# design.net
KiCad netlist of a schematic drawn in Altium Designer
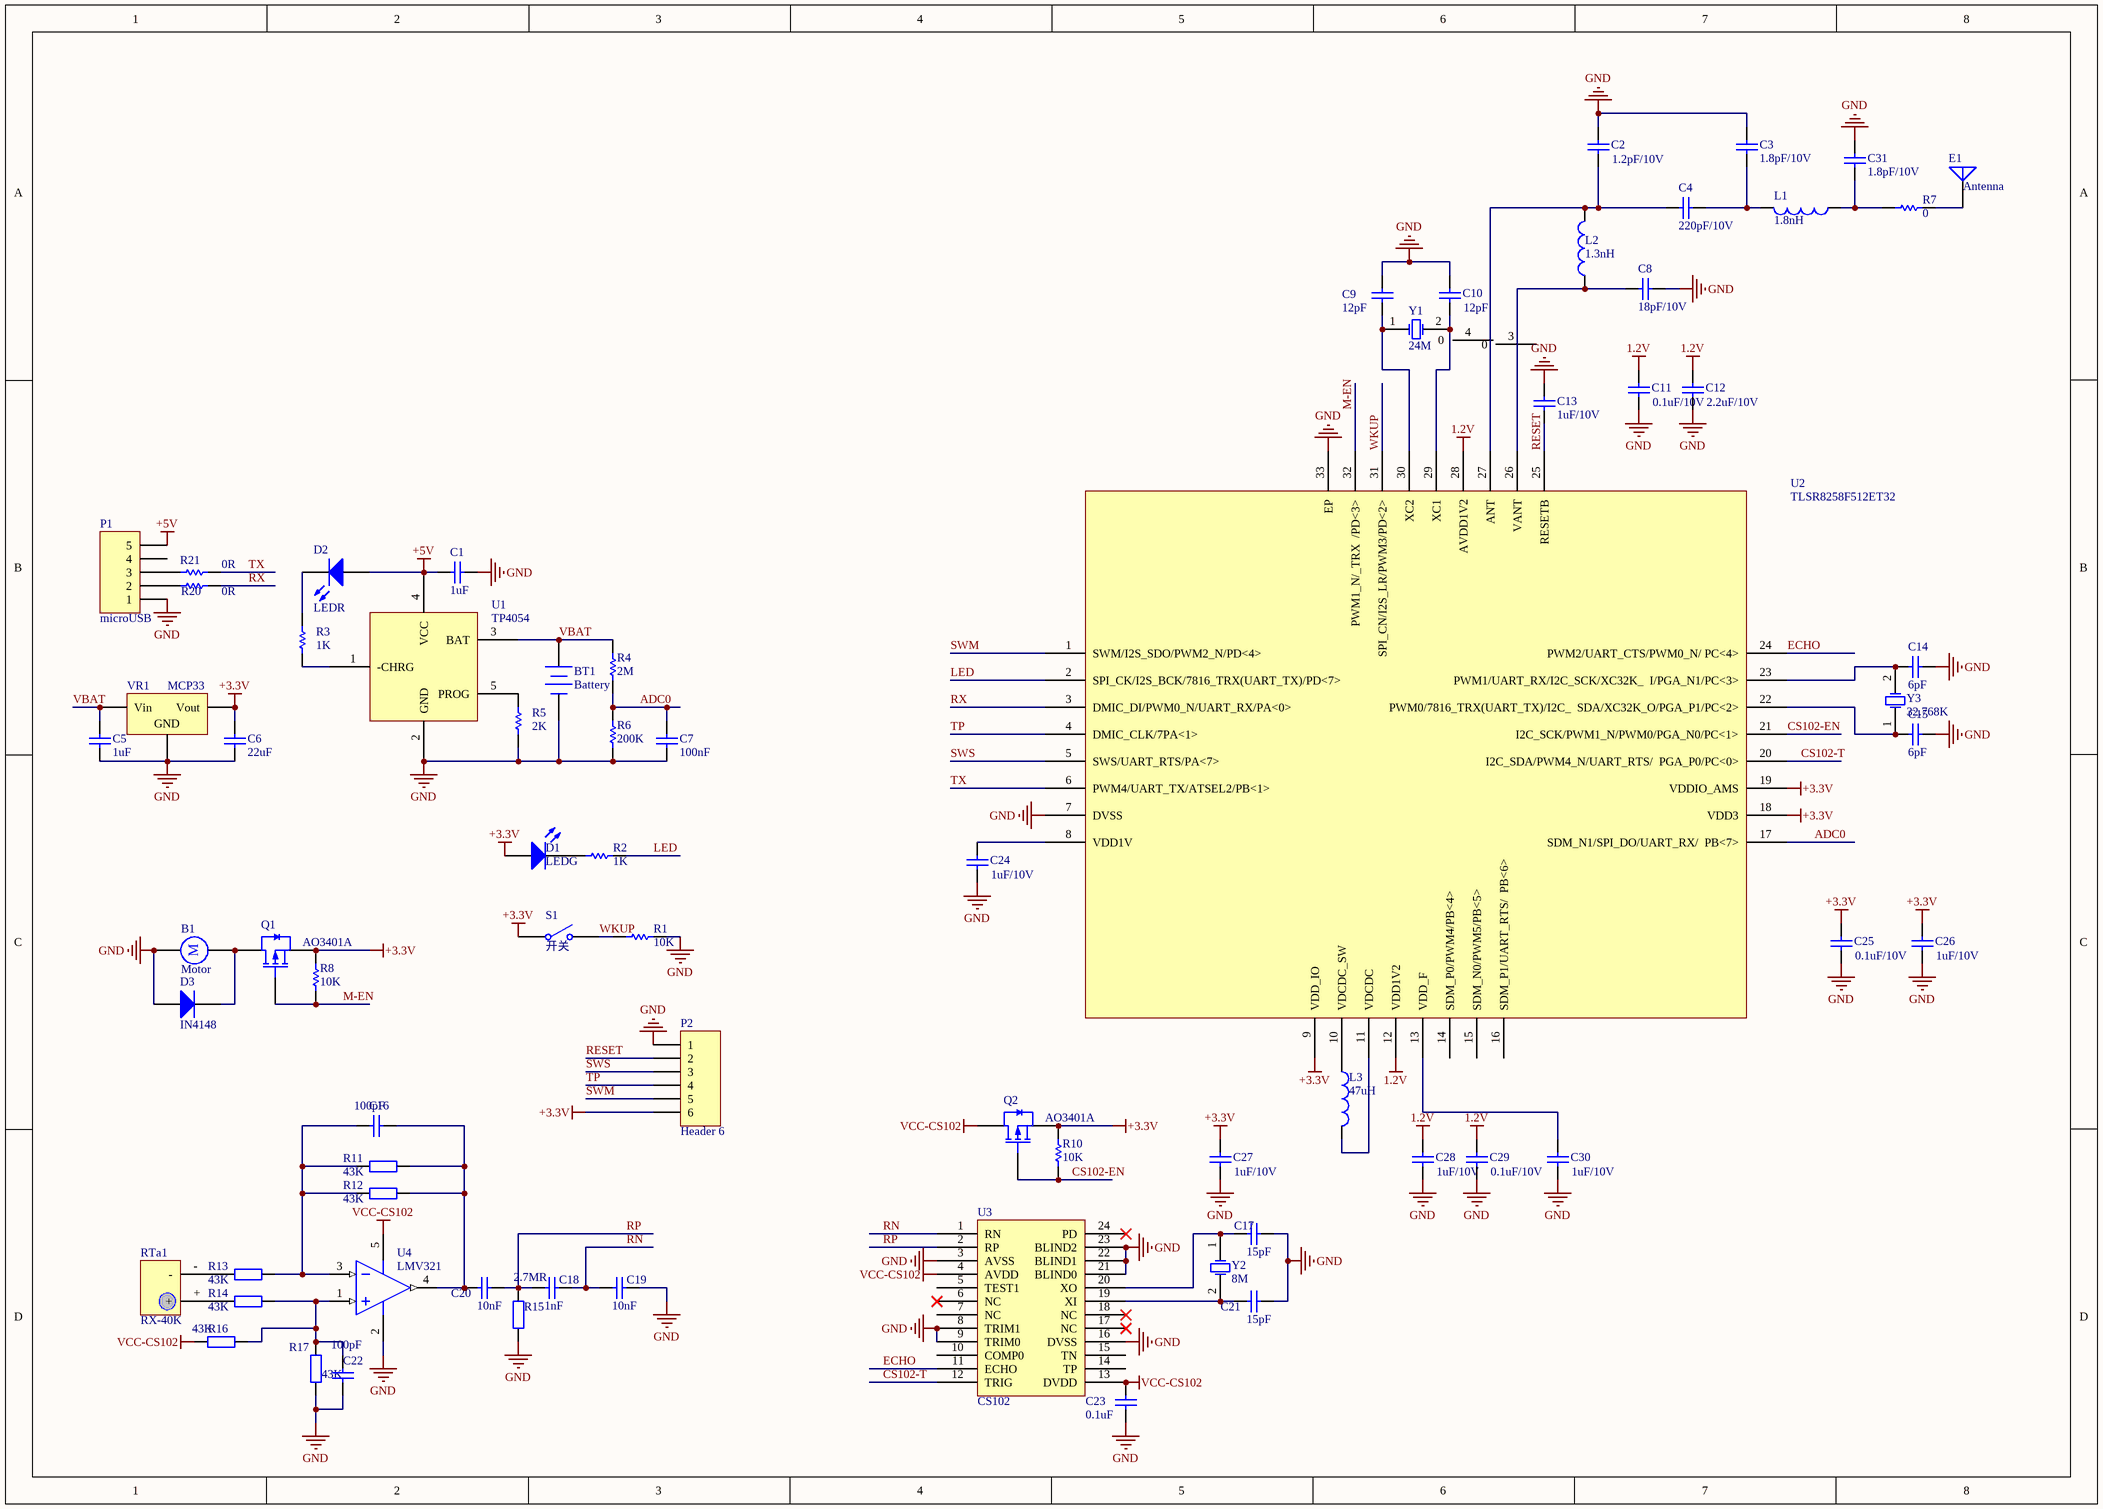
[diagram p0: 接收端原理图.SchDoc]

(export (version "E")
  (design (tool "Eeschema 10.0.6"))
  (components
    (comp (ref "B1")
      (value "Motor")
      (footprint "MOTO-40*44*114 - 3D")
      (description "Motor, General Kind")
      (fields (field (name "PUBLISHER") "Altium Limited"))
      (libsource (lib "Miscellaneous Devices") (part "Motor"))
    )
    (comp (ref "BT1")
      (value "Battery")
      (footprint "BT")
      (description "Multicell Battery")
      (fields (field (name "PUBLISHER") "Altium Limited"))
      (libsource (lib "Miscellaneous Devices") (part "Battery"))
    )
    (comp (ref "C1")
      (value "1uF")
      (description "Capacitor")
      (fields (field (name "PUBLISHER") "Altium Limited"))
      (libsource (lib "Miscellaneous Devices") (part "Cap"))
    )
    (comp (ref "C2")
      (value "1.2pF/10V")
      (footprint "0402")
      (description "Capacitor")
      (fields (field (name "PUBLISHER") "Altium Limited"))
      (libsource (lib "Miscellaneous Devices") (part "Cap"))
    )
    (comp (ref "C3")
      (value "1.8pF/10V")
      (footprint "0402")
      (description "Capacitor")
      (fields (field (name "PUBLISHER") "Altium Limited"))
      (libsource (lib "Miscellaneous Devices") (part "Cap"))
    )
    (comp (ref "C4")
      (value "220pF/10V")
      (footprint "0402")
      (description "Capacitor")
      (fields (field (name "PUBLISHER") "Altium Limited"))
      (libsource (lib "Miscellaneous Devices") (part "Cap"))
    )
    (comp (ref "C5")
      (value "1uF")
      (description "Capacitor")
      (fields (field (name "PUBLISHER") "Altium Limited"))
      (libsource (lib "Miscellaneous Devices") (part "Cap"))
    )
    (comp (ref "C6")
      (value "22uF")
      (description "Capacitor")
      (fields (field (name "PUBLISHER") "Altium Limited"))
      (libsource (lib "Miscellaneous Devices") (part "Cap"))
    )
    (comp (ref "C7")
      (value "100nF")
      (description "Capacitor")
      (fields (field (name "PUBLISHER") "Altium Limited"))
      (libsource (lib "Miscellaneous Devices") (part "Cap"))
    )
    (comp (ref "C8")
      (value "18pF/10V")
      (footprint "0402")
      (description "Capacitor")
      (fields (field (name "PUBLISHER") "Altium Limited"))
      (libsource (lib "Miscellaneous Devices") (part "Cap"))
    )
    (comp (ref "C9")
      (value "12pF")
      (footprint "0402")
      (description "Capacitor")
      (fields (field (name "PUBLISHER") "Altium Limited"))
      (libsource (lib "Miscellaneous Devices") (part "Cap"))
    )
    (comp (ref "C10")
      (value "12pF")
      (footprint "0402")
      (description "Capacitor")
      (fields (field (name "PUBLISHER") "Altium Limited"))
      (libsource (lib "Miscellaneous Devices") (part "Cap"))
    )
    (comp (ref "C11")
      (value "0.1uF/10V")
      (footprint "0402")
      (description "Capacitor")
      (fields (field (name "PUBLISHER") "Altium Limited"))
      (libsource (lib "Miscellaneous Devices") (part "Cap"))
    )
    (comp (ref "C12")
      (value "2.2uF/10V")
      (footprint "0402")
      (description "Capacitor")
      (fields (field (name "PUBLISHER") "Altium Limited"))
      (libsource (lib "Miscellaneous Devices") (part "Cap"))
    )
    (comp (ref "C13")
      (value "1uF/10V")
      (footprint "0402")
      (description "Capacitor")
      (fields (field (name "PUBLISHER") "Altium Limited"))
      (libsource (lib "Miscellaneous Devices") (part "Cap"))
    )
    (comp (ref "C14")
      (value "6pF")
      (footprint "0402")
      (description "Capacitor")
      (fields (field (name "PUBLISHER") "Altium Limited"))
      (libsource (lib "Miscellaneous Devices") (part "Cap"))
    )
    (comp (ref "C15")
      (value "6pF")
      (footprint "0402")
      (description "Capacitor")
      (fields (field (name "PUBLISHER") "Altium Limited"))
      (libsource (lib "Miscellaneous Devices") (part "Cap"))
    )
    (comp (ref "C16")
      (value "100pF")
      (footprint "0402")
      (description "Capacitor")
      (fields (field (name "PUBLISHER") "Altium Limited"))
      (libsource (lib "Miscellaneous Devices") (part "Cap"))
    )
    (comp (ref "C17")
      (value "15pF")
      (footprint "0402")
      (description "Capacitor")
      (fields (field (name "PUBLISHER") "Altium Limited"))
      (libsource (lib "Miscellaneous Devices") (part "Cap"))
    )
    (comp (ref "C18")
      (value "1nF")
      (footprint "0402")
      (description "Capacitor")
      (fields (field (name "PUBLISHER") "Altium Limited"))
      (libsource (lib "Miscellaneous Devices") (part "Cap"))
    )
    (comp (ref "C19")
      (value "10nF")
      (footprint "0402")
      (description "Capacitor")
      (fields (field (name "PUBLISHER") "Altium Limited"))
      (libsource (lib "Miscellaneous Devices") (part "Cap"))
    )
    (comp (ref "C20")
      (value "10nF")
      (footprint "0402")
      (description "Capacitor")
      (fields (field (name "PUBLISHER") "Altium Limited"))
      (libsource (lib "Miscellaneous Devices") (part "Cap"))
    )
    (comp (ref "C21")
      (value "15pF")
      (footprint "0402")
      (description "Capacitor")
      (fields (field (name "PUBLISHER") "Altium Limited"))
      (libsource (lib "Miscellaneous Devices") (part "Cap"))
    )
    (comp (ref "C22")
      (value "100pF")
      (footprint "0402")
      (description "Capacitor")
      (fields (field (name "PUBLISHER") "Altium Limited"))
      (libsource (lib "Miscellaneous Devices") (part "Cap"))
    )
    (comp (ref "C23")
      (value "0.1uF")
      (description "Capacitor")
      (fields (field (name "PUBLISHER") "Altium Limited"))
      (libsource (lib "Miscellaneous Devices") (part "Cap"))
    )
    (comp (ref "C24")
      (value "1uF/10V")
      (footprint "0402")
      (description "Capacitor")
      (fields (field (name "PUBLISHER") "Altium Limited"))
      (libsource (lib "Miscellaneous Devices") (part "Cap"))
    )
    (comp (ref "C25")
      (value "0.1uF/10V")
      (footprint "0402")
      (description "Capacitor")
      (fields (field (name "PUBLISHER") "Altium Limited"))
      (libsource (lib "Miscellaneous Devices") (part "Cap"))
    )
    (comp (ref "C26")
      (value "1uF/10V")
      (footprint "0402")
      (description "Capacitor")
      (fields (field (name "PUBLISHER") "Altium Limited"))
      (libsource (lib "Miscellaneous Devices") (part "Cap"))
    )
    (comp (ref "C27")
      (value "1uF/10V")
      (footprint "0402")
      (description "Capacitor")
      (fields (field (name "PUBLISHER") "Altium Limited"))
      (libsource (lib "Miscellaneous Devices") (part "Cap"))
    )
    (comp (ref "C28")
      (value "1uF/10V")
      (footprint "0402")
      (description "Capacitor")
      (fields (field (name "PUBLISHER") "Altium Limited"))
      (libsource (lib "Miscellaneous Devices") (part "Cap"))
    )
    (comp (ref "C29")
      (value "0.1uF/10V")
      (footprint "0402")
      (description "Capacitor")
      (fields (field (name "PUBLISHER") "Altium Limited"))
      (libsource (lib "Miscellaneous Devices") (part "Cap"))
    )
    (comp (ref "C30")
      (value "1uF/10V")
      (footprint "0402")
      (description "Capacitor")
      (fields (field (name "PUBLISHER") "Altium Limited"))
      (libsource (lib "Miscellaneous Devices") (part "Cap"))
    )
    (comp (ref "C31")
      (value "1.8pF/10V")
      (footprint "0402")
      (description "Capacitor")
      (fields (field (name "PUBLISHER") "Altium Limited"))
      (libsource (lib "Miscellaneous Devices") (part "Cap"))
    )
    (comp (ref "D1")
      (value "LEDG")
      (footprint "LED0603")
      (description "Typical INFRARED GaAs LED")
      (fields (field (name "PUBLISHER") "Altium Limited"))
      (libsource (lib "Miscellaneous Devices") (part "LED0"))
    )
    (comp (ref "D2")
      (value "LEDR")
      (footprint "LED0603")
      (description "Typical INFRARED GaAs LED")
      (fields (field (name "PUBLISHER") "Altium Limited"))
      (libsource (lib "Miscellaneous Devices") (part "LED0"))
    )
    (comp (ref "D3")
      (value "IN4148")
      (footprint "LED0603")
      (description "Default Diode")
      (fields (field (name "PUBLISHER") "Altium Limited"))
      (libsource (lib "Miscellaneous Devices") (part "Diode"))
    )
    (comp (ref "E1")
      (value "Antenna")
      (footprint "AN3216")
      (description "Generic Antenna")
      (fields (field (name "PUBLISHER") "Altium Limited"))
      (libsource (lib "Miscellaneous Devices") (part "Antenna"))
    )
    (comp (ref "L1")
      (value "1.8nH")
      (description "Inductor")
      (fields (field (name "PUBLISHER") "Altium Limited"))
      (libsource (lib "Miscellaneous Devices") (part "Inductor"))
    )
    (comp (ref "L2")
      (value "1.3nH")
      (description "Inductor")
      (fields (field (name "PUBLISHER") "Altium Limited"))
      (libsource (lib "Miscellaneous Devices") (part "Inductor"))
    )
    (comp (ref "L3")
      (value "47uH")
      (description "Inductor")
      (fields (field (name "PUBLISHER") "Altium Limited"))
      (libsource (lib "Miscellaneous Devices") (part "Inductor"))
    )
    (comp (ref "P1")
      (value "microUSB")
      (footprint "MICROUSB")
      (description "Header, 5-Pin")
      (fields (field (name "PUBLISHER") "Altium Limited"))
      (libsource (lib "Miscellaneous Connectors") (part "Header 5"))
    )
    (comp (ref "P2")
      (value "Header 6")
      (footprint "SIP6-1.27")
      (description "Header, 6-Pin")
      (fields (field (name "PUBLISHER") "Altium Limited"))
      (libsource (lib "Miscellaneous Connectors") (part "Header 6"))
    )
    (comp (ref "Q1")
      (value "AO3401A")
      (footprint "AO3401")
      (description "MOS(场效应管)")
      (libsource (lib "Miscellaneous Devices LC") (part "AO3401A P道沟 X13A15 SOT-23"))
    )
    (comp (ref "Q2")
      (value "AO3401A")
      (footprint "SOT23")
      (description "MOS(场效应管)")
      (libsource (lib "Miscellaneous Devices LC") (part "AO3401A P道沟 X13A15 SOT-23"))
    )
    (comp (ref "R1")
      (value "10K")
      (description "Resistor")
      (fields (field (name "PUBLISHER") "Altium Limited"))
      (libsource (lib "Miscellaneous Devices") (part "Res1"))
    )
    (comp (ref "R2")
      (value "1K")
      (description "Resistor")
      (fields (field (name "PUBLISHER") "Altium Limited"))
      (libsource (lib "Miscellaneous Devices") (part "Res1"))
    )
    (comp (ref "R3")
      (value "1K")
      (description "Resistor")
      (fields (field (name "PUBLISHER") "Altium Limited"))
      (libsource (lib "Miscellaneous Devices") (part "Res1"))
    )
    (comp (ref "R4")
      (value "2M")
      (description "Resistor")
      (fields (field (name "PUBLISHER") "Altium Limited"))
      (libsource (lib "Miscellaneous Devices") (part "Res1"))
    )
    (comp (ref "R5")
      (value "2K")
      (description "Resistor")
      (fields (field (name "PUBLISHER") "Altium Limited"))
      (libsource (lib "Miscellaneous Devices") (part "Res1"))
    )
    (comp (ref "R6")
      (value "200K")
      (description "Resistor")
      (fields (field (name "PUBLISHER") "Altium Limited"))
      (libsource (lib "Miscellaneous Devices") (part "Res1"))
    )
    (comp (ref "R7")
      (value "0")
      (description "Resistor")
      (fields (field (name "PUBLISHER") "Altium Limited"))
      (libsource (lib "Miscellaneous Devices") (part "Res1"))
    )
    (comp (ref "R8")
      (value "10K")
      (description "Resistor")
      (fields (field (name "PUBLISHER") "Altium Limited"))
      (libsource (lib "Miscellaneous Devices") (part "Res1"))
    )
    (comp (ref "R10")
      (value "10K")
      (description "Resistor")
      (fields (field (name "PUBLISHER") "Altium Limited"))
      (libsource (lib "Miscellaneous Devices") (part "Res1"))
    )
    (comp (ref "R11")
      (value "43K")
      (footprint "0402")
      (description "Resistor")
      (fields (field (name "PUBLISHER") "Altium Limited"))
      (libsource (lib "") (part "Res2_1"))
    )
    (comp (ref "R12")
      (value "43K")
      (footprint "0402")
      (description "Resistor")
      (fields (field (name "PUBLISHER") "Altium Limited"))
      (libsource (lib "") (part "Res2_1"))
    )
    (comp (ref "R13")
      (value "43K")
      (footprint "0402")
      (description "Resistor")
      (fields (field (name "PUBLISHER") "Altium Limited"))
      (libsource (lib "") (part "Res2_1"))
    )
    (comp (ref "R14")
      (value "43K")
      (footprint "0402")
      (description "Resistor")
      (fields (field (name "PUBLISHER") "Altium Limited"))
      (libsource (lib "") (part "Res2_1"))
    )
    (comp (ref "R15")
      (value "2.7MR")
      (footprint "0402")
      (description "Resistor")
      (fields (field (name "PUBLISHER") "Altium Limited"))
      (libsource (lib "Miscellaneous Devices") (part "Res2"))
    )
    (comp (ref "R16")
      (value "43K")
      (footprint "0402")
      (description "Resistor")
      (fields (field (name "PUBLISHER") "Altium Limited"))
      (libsource (lib "") (part "Res2_2"))
    )
    (comp (ref "R17")
      (value "43K")
      (footprint "0402")
      (description "Resistor")
      (fields (field (name "PUBLISHER") "Altium Limited"))
      (libsource (lib "Miscellaneous Devices") (part "Res2"))
    )
    (comp (ref "R20")
      (value "0R")
      (description "Resistor")
      (fields (field (name "PUBLISHER") "Altium Limited"))
      (libsource (lib "Miscellaneous Devices") (part "Res1"))
    )
    (comp (ref "R21")
      (value "0R")
      (description "Resistor")
      (fields (field (name "PUBLISHER") "Altium Limited"))
      (libsource (lib "Miscellaneous Devices") (part "Res1"))
    )
    (comp (ref "RTa1") (value "RX-40K") (footprint "US-10mm") (libsource (lib "USLib") (part "TC40K")))
    (comp (ref "S1")
      (value "开关")
      (footprint "SW3x6x5")
      (description "Single-Pole, Single-Throw Switch")
      (fields (field (name "PUBLISHER") "Altium Limited"))
      (libsource (lib "Miscellaneous Devices") (part "SW-SPST"))
    )
    (comp (ref "U1") (value "TP4054") (footprint "TP4054") (libsource (lib "Schlib1") (part "TP4054")))
    (comp (ref "U2")
      (value "TLSR8258F512ET32")
      (footprint "QFN-32")
      (libsource (lib "stm32") (part "TLSR8258F512ET32"))
    )
    (comp (ref "U3") (value "CS102") (footprint "TSSOP24") (libsource (lib "USLib") (part "CS100")))
    (comp (ref "U4")
      (value "LMV321")
      (footprint "MF05A_N")
      (description "General Purpose, Low Voltage, Rail-to-Rail Output Operational Amplifiers")
      (fields
        (field (name "PARTNUMBER") "LMV321M5")
        (field (name "MANUFACTURER") "National Semiconductor")
        (field (name "PUBLISHER") "Altium Limited")
      )
      (libsource (lib "NSC Amplifier") (part "LMV321M5"))
    )
    (comp (ref "VR1")
      (value "MCP33")
      (footprint "SOT23")
      (description "Voltage Regulator")
      (fields (field (name "PUBLISHER") "Altium Limited"))
      (libsource (lib "Miscellaneous Devices") (part "Volt Reg"))
    )
    (comp (ref "Y1")
      (value "24M")
      (footprint "XTAL4TN_3225")
      (description "Crystal Oscillator")
      (fields (field (name "PUBLISHER") "Altium Limited"))
      (libsource (lib "") (part "XTAL_1"))
    )
    (comp (ref "Y2")
      (value "8M")
      (footprint "5032")
      (description "Crystal Oscillator")
      (fields (field (name "PUBLISHER") "Altium Limited"))
      (libsource (lib "Miscellaneous Devices") (part "XTAL"))
    )
    (comp (ref "Y3")
      (value "32.768K")
      (footprint "S3215")
      (description "Crystal Oscillator")
      (fields (field (name "PUBLISHER") "Altium Limited"))
      (libsource (lib "Miscellaneous Devices") (part "XTAL"))
    )
  )
  (nets
    (net (code "1") (name "+3.3V") (class "Default")
      (node (ref "C25") (pin "2") (pinfunction "2_2") (pintype "passive"))
      (node (ref "C26") (pin "2") (pinfunction "2_2") (pintype "passive"))
      (node (ref "C27") (pin "2") (pinfunction "2_2") (pintype "passive"))
      (node (ref "C6") (pin "1") (pinfunction "1_1") (pintype "passive"))
      (node (ref "D1") (pin "1") (pinfunction "A_1") (pintype "passive"))
      (node (ref "P2") (pin "6") (pinfunction "6_6") (pintype "passive"))
      (node (ref "Q1") (pin "2") (pinfunction "S_2") (pintype "passive"))
      (node (ref "Q2") (pin "2") (pinfunction "S_2") (pintype "passive"))
      (node (ref "R10") (pin "2") (pinfunction "2_2") (pintype "passive"))
      (node (ref "R8") (pin "2") (pinfunction "2_2") (pintype "passive"))
      (node (ref "S1") (pin "1") (pinfunction "COMMON_1") (pintype "passive"))
      (node (ref "U2") (pin "18") (pinfunction "VDD3_18") (pintype "passive"))
      (node (ref "U2") (pin "19") (pinfunction "VDDIO_AMS_19") (pintype "passive"))
      (node (ref "U2") (pin "9") (pinfunction "VDD_IO_9") (pintype "passive"))
      (node (ref "VR1") (pin "3") (pinfunction "Vout_3") (pintype "passive"))
    )
    (net (code "2") (name "+5V") (class "Default")
      (node (ref "C1") (pin "2") (pinfunction "2_2") (pintype "passive"))
      (node (ref "D2") (pin "1") (pinfunction "A_1") (pintype "passive"))
      (node (ref "P1") (pin "5") (pinfunction "5_5") (pintype "passive"))
      (node (ref "U1") (pin "4") (pinfunction "VCC_4") (pintype "passive"))
    )
    (net (code "3") (name "/ADC0") (class "Default")
      (node (ref "C7") (pin "2") (pinfunction "2_2") (pintype "passive"))
      (node (ref "R4") (pin "1") (pinfunction "1_1") (pintype "passive"))
      (node (ref "R6") (pin "2") (pinfunction "2_2") (pintype "passive"))
      (node (ref "U2") (pin "17") (pinfunction "SDM_N1/SPI_DO/UART_RX/__PB<7>_17") (pintype "passive"))
    )
    (net (code "4") (name "/CS102-EN") (class "Default")
      (node (ref "Q2") (pin "1") (pinfunction "G_1") (pintype "passive"))
      (node (ref "R10") (pin "1") (pinfunction "1_1") (pintype "passive"))
      (node (ref "U2") (pin "21") (pinfunction "I2C_SCK/PWM1_N/PWM0/PGA_N0/PC<1>_21") (pintype "passive"))
    )
    (net (code "5") (name "/CS102-T") (class "Default")
      (node (ref "U2") (pin "20") (pinfunction "I2C_SDA/PWM4_N/UART_RTS/__PGA_P0/PC<0>_20") (pintype "passive"))
      (node (ref "U3") (pin "12") (pinfunction "TRIG_12") (pintype "passive"))
    )
    (net (code "6") (name "/ECHO") (class "Default")
      (node (ref "U2") (pin "24") (pinfunction "PWM2/UART_CTS/PWM0_N/_PC<4>_24") (pintype "passive"))
      (node (ref "U3") (pin "11") (pinfunction "ECHO_11") (pintype "passive"))
    )
    (net (code "7") (name "/LED") (class "Default")
      (node (ref "R2") (pin "1") (pinfunction "1_1") (pintype "passive"))
      (node (ref "U2") (pin "2") (pinfunction "SPI_CK/I2S_BCK/7816_TRX(UART_TX)/PD<7>_2") (pintype "passive"))
    )
    (net (code "8") (name "/M-EN") (class "Default")
      (node (ref "Q1") (pin "1") (pinfunction "G_1") (pintype "passive"))
      (node (ref "R8") (pin "1") (pinfunction "1_1") (pintype "passive"))
      (node (ref "U2") (pin "32") (pinfunction "PWM1_N/_TRX__/PD<3>_32") (pintype "passive"))
    )
    (net (code "9") (name "/RESET") (class "Default")
      (node (ref "C13") (pin "2") (pinfunction "2_2") (pintype "passive"))
      (node (ref "P2") (pin "2") (pinfunction "2_2") (pintype "passive"))
      (node (ref "U2") (pin "25") (pinfunction "RESETB_25") (pintype "passive"))
    )
    (net (code "10") (name "/RN") (class "Default")
      (node (ref "C18") (pin "2") (pinfunction "2_2") (pintype "passive"))
      (node (ref "C19") (pin "1") (pinfunction "1_1") (pintype "passive"))
      (node (ref "U3") (pin "1") (pinfunction "RN_1") (pintype "passive"))
    )
    (net (code "11") (name "/RP") (class "Default")
      (node (ref "C18") (pin "1") (pinfunction "1_1") (pintype "passive"))
      (node (ref "C20") (pin "2") (pinfunction "2_2") (pintype "passive"))
      (node (ref "R15") (pin "2") (pinfunction "2_2") (pintype "passive"))
      (node (ref "U3") (pin "2") (pinfunction "RP_2") (pintype "passive"))
    )
    (net (code "12") (name "/RX") (class "Default")
      (node (ref "R20") (pin "1") (pinfunction "1_1") (pintype "passive"))
      (node (ref "U2") (pin "3") (pinfunction "DMIC_DI/PWM0_N/UART_RX/PA<0>_3") (pintype "passive"))
    )
    (net (code "13") (name "/SWM") (class "Default")
      (node (ref "P2") (pin "5") (pinfunction "5_5") (pintype "passive"))
      (node (ref "U2") (pin "1") (pinfunction "SWM/I2S_SDO/PWM2_N/PD<4>_1") (pintype "passive"))
    )
    (net (code "14") (name "/SWS") (class "Default")
      (node (ref "P2") (pin "3") (pinfunction "3_3") (pintype "passive"))
      (node (ref "U2") (pin "5") (pinfunction "SWS/UART_RTS/PA<7>_5") (pintype "passive"))
    )
    (net (code "15") (name "/TP") (class "Default")
      (node (ref "P2") (pin "4") (pinfunction "4_4") (pintype "passive"))
      (node (ref "U2") (pin "4") (pinfunction "DMIC_CLK/7PA<1>_4") (pintype "passive"))
    )
    (net (code "16") (name "/TX") (class "Default")
      (node (ref "R21") (pin "1") (pinfunction "1_1") (pintype "passive"))
      (node (ref "U2") (pin "6") (pinfunction "PWM4/UART_TX/ATSEL2/PB<1>_6") (pintype "passive"))
    )
    (net (code "17") (name "/VBAT") (class "Default")
      (node (ref "BT1") (pin "1") (pinfunction "+_1") (pintype "passive"))
      (node (ref "C5") (pin "1") (pinfunction "1_1") (pintype "passive"))
      (node (ref "R4") (pin "2") (pinfunction "2_2") (pintype "passive"))
      (node (ref "U1") (pin "3") (pinfunction "BAT_3") (pintype "passive"))
      (node (ref "VR1") (pin "1") (pinfunction "Vin_1") (pintype "passive"))
    )
    (net (code "18") (name "/WKUP") (class "Default")
      (node (ref "R1") (pin "2") (pinfunction "2_2") (pintype "passive"))
      (node (ref "S1") (pin "2") (pinfunction "NO_2") (pintype "passive"))
      (node (ref "U2") (pin "31") (pinfunction "SPI_CN/I2S_LR/PWM3/PD<2>_31") (pintype "passive"))
    )
    (net (code "19") (name "1.2V") (class "Default")
      (node (ref "C11") (pin "2") (pinfunction "2_2") (pintype "passive"))
      (node (ref "C12") (pin "2") (pinfunction "2_2") (pintype "passive"))
      (node (ref "C28") (pin "2") (pinfunction "2_2") (pintype "passive"))
      (node (ref "C29") (pin "2") (pinfunction "2_2") (pintype "passive"))
      (node (ref "U2") (pin "12") (pinfunction "VDD1V2_12") (pintype "passive"))
      (node (ref "U2") (pin "28") (pinfunction "AVDD1V2_28") (pintype "passive"))
    )
    (net (code "20") (name "GND") (class "Default")
      (node (ref "B1") (pin "1") (pinfunction "1_1") (pintype "passive"))
      (node (ref "BT1") (pin "2") (pinfunction "-_2") (pintype "passive"))
      (node (ref "C1") (pin "1") (pinfunction "1_1") (pintype "passive"))
      (node (ref "C10") (pin "2") (pinfunction "2_2") (pintype "passive"))
      (node (ref "C11") (pin "1") (pinfunction "1_1") (pintype "passive"))
      (node (ref "C12") (pin "1") (pinfunction "1_1") (pintype "passive"))
      (node (ref "C13") (pin "1") (pinfunction "1_1") (pintype "passive"))
      (node (ref "C14") (pin "1") (pinfunction "1_1") (pintype "passive"))
      (node (ref "C15") (pin "1") (pinfunction "1_1") (pintype "passive"))
      (node (ref "C17") (pin "2") (pinfunction "2_2") (pintype "passive"))
      (node (ref "C19") (pin "2") (pinfunction "2_2") (pintype "passive"))
      (node (ref "C2") (pin "2") (pinfunction "2_2") (pintype "passive"))
      (node (ref "C21") (pin "2") (pinfunction "2_2") (pintype "passive"))
      (node (ref "C22") (pin "1") (pinfunction "1_1") (pintype "passive"))
      (node (ref "C23") (pin "1") (pinfunction "1_1") (pintype "passive"))
      (node (ref "C24") (pin "1") (pinfunction "1_1") (pintype "passive"))
      (node (ref "C25") (pin "1") (pinfunction "1_1") (pintype "passive"))
      (node (ref "C26") (pin "1") (pinfunction "1_1") (pintype "passive"))
      (node (ref "C27") (pin "1") (pinfunction "1_1") (pintype "passive"))
      (node (ref "C28") (pin "1") (pinfunction "1_1") (pintype "passive"))
      (node (ref "C29") (pin "1") (pinfunction "1_1") (pintype "passive"))
      (node (ref "C3") (pin "1") (pinfunction "1_1") (pintype "passive"))
      (node (ref "C30") (pin "1") (pinfunction "1_1") (pintype "passive"))
      (node (ref "C31") (pin "1") (pinfunction "1_1") (pintype "passive"))
      (node (ref "C5") (pin "2") (pinfunction "2_2") (pintype "passive"))
      (node (ref "C6") (pin "2") (pinfunction "2_2") (pintype "passive"))
      (node (ref "C7") (pin "1") (pinfunction "1_1") (pintype "passive"))
      (node (ref "C8") (pin "1") (pinfunction "1_1") (pintype "passive"))
      (node (ref "C9") (pin "2") (pinfunction "2_2") (pintype "passive"))
      (node (ref "D3") (pin "1") (pinfunction "A_1") (pintype "passive"))
      (node (ref "P1") (pin "1") (pinfunction "1_1") (pintype "passive"))
      (node (ref "P2") (pin "1") (pinfunction "1_1") (pintype "passive"))
      (node (ref "R1") (pin "1") (pinfunction "1_1") (pintype "passive"))
      (node (ref "R15") (pin "1") (pinfunction "1_1") (pintype "passive"))
      (node (ref "R17") (pin "1") (pinfunction "1_1") (pintype "passive"))
      (node (ref "R5") (pin "1") (pinfunction "1_1") (pintype "passive"))
      (node (ref "R6") (pin "1") (pinfunction "1_1") (pintype "passive"))
      (node (ref "U1") (pin "2") (pinfunction "GND_2") (pintype "passive"))
      (node (ref "U2") (pin "33") (pinfunction "EP_33") (pintype "passive"))
      (node (ref "U2") (pin "7") (pinfunction "DVSS_7") (pintype "passive"))
      (node (ref "U3") (pin "16") (pinfunction "DVSS_16") (pintype "passive"))
      (node (ref "U3") (pin "21") (pinfunction "BLIND0_21") (pintype "passive"))
      (node (ref "U3") (pin "22") (pinfunction "BLIND1_22") (pintype "passive"))
      (node (ref "U3") (pin "23") (pinfunction "BLIND2_23") (pintype "passive"))
      (node (ref "U3") (pin "3") (pinfunction "AVSS_3") (pintype "passive"))
      (node (ref "U3") (pin "8") (pinfunction "TRIM1_8") (pintype "passive"))
      (node (ref "U3") (pin "9") (pinfunction "TRIM0_9") (pintype "passive"))
      (node (ref "U4") (pin "2") (pinfunction "V-_2") (pintype "power_in"))
      (node (ref "VR1") (pin "2") (pinfunction "GND_2") (pintype "passive"))
    )
    (net (code "21") (name "Net-(C3-Pad2)") (class "Default")
      (node (ref "C3") (pin "2") (pinfunction "2_2") (pintype "passive"))
      (node (ref "C4") (pin "1") (pinfunction "1_1") (pintype "passive"))
      (node (ref "L1") (pin "2") (pinfunction "2_2") (pintype "passive"))
    )
    (net (code "22") (name "Net-(C31-Pad2)") (class "Default")
      (node (ref "C31") (pin "2") (pinfunction "2_2") (pintype "passive"))
      (node (ref "L1") (pin "1") (pinfunction "1_1") (pintype "passive"))
      (node (ref "R7") (pin "2") (pinfunction "2_2") (pintype "passive"))
    )
    (net (code "23") (name "Net-(D1-K)") (class "Default")
      (node (ref "D1") (pin "2") (pinfunction "K_2") (pintype "passive"))
      (node (ref "R2") (pin "2") (pinfunction "2_2") (pintype "passive"))
    )
    (net (code "24") (name "Net-(D2-K)") (class "Default")
      (node (ref "D2") (pin "2") (pinfunction "K_2") (pintype "passive"))
      (node (ref "R3") (pin "2") (pinfunction "2_2") (pintype "passive"))
    )
    (net (code "25") (name "Net-(D3-K)") (class "Default")
      (node (ref "B1") (pin "2") (pinfunction "2_2") (pintype "passive"))
      (node (ref "D3") (pin "2") (pinfunction "K_2") (pintype "passive"))
      (node (ref "Q1") (pin "3") (pinfunction "D_3") (pintype "passive"))
    )
    (net (code "26") (name "Net-(E1-A)") (class "Default")
      (node (ref "E1") (pin "1") (pinfunction "A_1") (pintype "passive"))
      (node (ref "R7") (pin "1") (pinfunction "1_1") (pintype "passive"))
    )
    (net (code "27") (name "Net-(P1-Pad2)") (class "Default")
      (node (ref "P1") (pin "2") (pinfunction "2_2") (pintype "passive"))
      (node (ref "R20") (pin "2") (pinfunction "2_2") (pintype "passive"))
    )
    (net (code "28") (name "Net-(P1-Pad3)") (class "Default")
      (node (ref "P1") (pin "3") (pinfunction "3_3") (pintype "passive"))
      (node (ref "R21") (pin "2") (pinfunction "2_2") (pintype "passive"))
    )
    (net (code "29") (name "Net-(R13-Pad1)") (class "Default")
      (node (ref "R13") (pin "1") (pinfunction "1_1") (pintype "passive"))
      (node (ref "RTa1") (pin "-") (pinfunction "-_-") (pintype "passive"))
    )
    (net (code "30") (name "Net-(R14-Pad1)") (class "Default")
      (node (ref "R14") (pin "1") (pinfunction "1_1") (pintype "passive"))
      (node (ref "RTa1") (pin "+") (pinfunction "+_+") (pintype "passive"))
    )
    (net (code "31") (name "Net-(U1--CHRG)") (class "Default")
      (node (ref "R3") (pin "1") (pinfunction "1_1") (pintype "passive"))
      (node (ref "U1") (pin "1") (pinfunction "-CHRG_1") (pintype "passive"))
    )
    (net (code "32") (name "Net-(U1-PROG)") (class "Default")
      (node (ref "R5") (pin "2") (pinfunction "2_2") (pintype "passive"))
      (node (ref "U1") (pin "5") (pinfunction "PROG_5") (pintype "passive"))
    )
    (net (code "33") (name "Net-(U2-ANT)") (class "Default")
      (node (ref "C2") (pin "1") (pinfunction "1_1") (pintype "passive"))
      (node (ref "C4") (pin "2") (pinfunction "2_2") (pintype "passive"))
      (node (ref "L2") (pin "2") (pinfunction "2_2") (pintype "passive"))
      (node (ref "U2") (pin "27") (pinfunction "ANT_27") (pintype "passive"))
    )
    (net (code "34") (name "Net-(U2-PWM0{slash}7816_TRX(UART_TX){slash}I2C___SDA{slash}XC32K_O{slash}PGA_P1{slash}PC<2>)") (class "Default")
      (node (ref "C15") (pin "2") (pinfunction "2_2") (pintype "passive"))
      (node (ref "U2") (pin "22") (pinfunction "PWM0/7816_TRX(UART_TX)/I2C___SDA/XC32K_O/PGA_P1/PC<2>_22") (pintype "passive"))
      (node (ref "Y3") (pin "1") (pinfunction "OSC1_1") (pintype "passive"))
    )
    (net (code "35") (name "Net-(U2-PWM1{slash}UART_RX{slash}I2C_SCK{slash}XC32K___I{slash}PGA_N1{slash}PC<3>)") (class "Default")
      (node (ref "C14") (pin "2") (pinfunction "2_2") (pintype "passive"))
      (node (ref "U2") (pin "23") (pinfunction "PWM1/UART_RX/I2C_SCK/XC32K___I/PGA_N1/PC<3>_23") (pintype "passive"))
      (node (ref "Y3") (pin "2") (pinfunction "OSC2_2") (pintype "passive"))
    )
    (net (code "36") (name "Net-(U2-VANT)") (class "Default")
      (node (ref "C8") (pin "2") (pinfunction "2_2") (pintype "passive"))
      (node (ref "L2") (pin "1") (pinfunction "1_1") (pintype "passive"))
      (node (ref "U2") (pin "26") (pinfunction "VANT_26") (pintype "passive"))
    )
    (net (code "37") (name "Net-(U2-VDCDC)") (class "Default")
      (node (ref "L3") (pin "2") (pinfunction "2_2") (pintype "passive"))
      (node (ref "U2") (pin "11") (pinfunction "VDCDC_11") (pintype "passive"))
    )
    (net (code "38") (name "Net-(U2-VDCDC_SW)") (class "Default")
      (node (ref "L3") (pin "1") (pinfunction "1_1") (pintype "passive"))
      (node (ref "U2") (pin "10") (pinfunction "VDCDC_SW_10") (pintype "passive"))
    )
    (net (code "39") (name "Net-(U2-VDD1V)") (class "Default")
      (node (ref "C24") (pin "2") (pinfunction "2_2") (pintype "passive"))
      (node (ref "U2") (pin "8") (pinfunction "VDD1V_8") (pintype "passive"))
    )
    (net (code "40") (name "Net-(U2-VDD_F)") (class "Default")
      (node (ref "C30") (pin "2") (pinfunction "2_2") (pintype "passive"))
      (node (ref "U2") (pin "13") (pinfunction "VDD_F_13") (pintype "passive"))
    )
    (net (code "41") (name "Net-(U2-XC1)") (class "Default")
      (node (ref "C10") (pin "1") (pinfunction "1_1") (pintype "passive"))
      (node (ref "U2") (pin "29") (pinfunction "XC1_29") (pintype "passive"))
      (node (ref "Y1") (pin "2") (pinfunction "OSC2_2") (pintype "passive"))
    )
    (net (code "42") (name "Net-(U2-XC2)") (class "Default")
      (node (ref "C9") (pin "1") (pinfunction "1_1") (pintype "passive"))
      (node (ref "U2") (pin "30") (pinfunction "XC2_30") (pintype "passive"))
      (node (ref "Y1") (pin "1") (pinfunction "OSC1_1") (pintype "passive"))
    )
    (net (code "43") (name "Net-(U3-XI)") (class "Default")
      (node (ref "C21") (pin "1") (pinfunction "1_1") (pintype "passive"))
      (node (ref "U3") (pin "19") (pinfunction "XI_19") (pintype "passive"))
      (node (ref "Y2") (pin "2") (pinfunction "OSC2_2") (pintype "passive"))
    )
    (net (code "44") (name "Net-(U3-XO)") (class "Default")
      (node (ref "C17") (pin "1") (pinfunction "1_1") (pintype "passive"))
      (node (ref "U3") (pin "20") (pinfunction "XO_20") (pintype "passive"))
      (node (ref "Y2") (pin "1") (pinfunction "OSC1_1") (pintype "passive"))
    )
    (net (code "45") (name "Net-(U4-IN+)") (class "Default")
      (node (ref "C22") (pin "2") (pinfunction "2_2") (pintype "passive"))
      (node (ref "R14") (pin "2") (pinfunction "2_2") (pintype "passive"))
      (node (ref "R16") (pin "1") (pinfunction "1_1") (pintype "passive"))
      (node (ref "R17") (pin "2") (pinfunction "2_2") (pintype "passive"))
      (node (ref "U4") (pin "1") (pinfunction "IN+_1") (pintype "input"))
    )
    (net (code "46") (name "Net-(U4-IN-)") (class "Default")
      (node (ref "C16") (pin "2") (pinfunction "2_2") (pintype "passive"))
      (node (ref "R11") (pin "1") (pinfunction "1_1") (pintype "passive"))
      (node (ref "R12") (pin "1") (pinfunction "1_1") (pintype "passive"))
      (node (ref "R13") (pin "2") (pinfunction "2_2") (pintype "passive"))
      (node (ref "U4") (pin "3") (pinfunction "IN-_3") (pintype "input"))
    )
    (net (code "47") (name "Net-(U4-OUT)") (class "Default")
      (node (ref "C16") (pin "1") (pinfunction "1_1") (pintype "passive"))
      (node (ref "C20") (pin "1") (pinfunction "1_1") (pintype "passive"))
      (node (ref "R11") (pin "2") (pinfunction "2_2") (pintype "passive"))
      (node (ref "R12") (pin "2") (pinfunction "2_2") (pintype "passive"))
      (node (ref "U4") (pin "4") (pinfunction "OUT_4") (pintype "output"))
    )
    (net (code "48") (name "VCC-CS102") (class "Default")
      (node (ref "C23") (pin "2") (pinfunction "2_2") (pintype "passive"))
      (node (ref "Q2") (pin "3") (pinfunction "D_3") (pintype "passive"))
      (node (ref "R16") (pin "2") (pinfunction "2_2") (pintype "passive"))
      (node (ref "U3") (pin "13") (pinfunction "DVDD_13") (pintype "passive"))
      (node (ref "U3") (pin "4") (pinfunction "AVDD_4") (pintype "passive"))
      (node (ref "U4") (pin "5") (pinfunction "V+_5") (pintype "power_in"))
    )
    (net (code "49") (name "unconnected-(P1-Pad4)") (class "Default")
      (node (ref "P1") (pin "4") (pinfunction "4_4") (pintype "passive"))
    )
    (net (code "50") (name "unconnected-(U2-SDM_N0{slash}PWM5{slash}PB<5>-Pad15)") (class "Default")
      (node (ref "U2") (pin "15") (pinfunction "SDM_N0/PWM5/PB<5>_15") (pintype "passive"))
    )
    (net (code "51") (name "unconnected-(U2-SDM_P0{slash}PWM4{slash}PB<4>-Pad14)") (class "Default")
      (node (ref "U2") (pin "14") (pinfunction "SDM_P0/PWM4/PB<4>_14") (pintype "passive"))
    )
    (net (code "52") (name "unconnected-(U2-SDM_P1{slash}UART_RTS{slash}__PB<6>-Pad16)") (class "Default")
      (node (ref "U2") (pin "16") (pinfunction "SDM_P1/UART_RTS/__PB<6>_16") (pintype "passive"))
    )
    (net (code "53") (name "unconnected-(U3-COMP0-Pad10)") (class "Default")
      (node (ref "U3") (pin "10") (pinfunction "COMP0_10") (pintype "passive"))
    )
    (net (code "54") (name "unconnected-(U3-NC-Pad6)") (class "Default")
      (node (ref "U3") (pin "6") (pinfunction "NC_6") (pintype "passive+no_connect"))
    )
    (net (code "55") (name "unconnected-(U3-NC-Pad7)") (class "Default")
      (node (ref "U3") (pin "7") (pinfunction "NC_7") (pintype "passive"))
    )
    (net (code "56") (name "unconnected-(U3-NC-Pad17)") (class "Default")
      (node (ref "U3") (pin "17") (pinfunction "NC_17") (pintype "passive+no_connect"))
    )
    (net (code "57") (name "unconnected-(U3-NC-Pad18)") (class "Default")
      (node (ref "U3") (pin "18") (pinfunction "NC_18") (pintype "passive+no_connect"))
    )
    (net (code "58") (name "unconnected-(U3-PD-Pad24)") (class "Default")
      (node (ref "U3") (pin "24") (pinfunction "PD_24") (pintype "passive+no_connect"))
    )
    (net (code "59") (name "unconnected-(U3-TEST1-Pad5)") (class "Default")
      (node (ref "U3") (pin "5") (pinfunction "TEST1_5") (pintype "passive"))
    )
    (net (code "60") (name "unconnected-(U3-TN-Pad15)") (class "Default")
      (node (ref "U3") (pin "15") (pinfunction "TN_15") (pintype "passive"))
    )
    (net (code "61") (name "unconnected-(U3-TP-Pad14)") (class "Default")
      (node (ref "U3") (pin "14") (pinfunction "TP_14") (pintype "passive"))
    )
    (net (code "62") (name "unconnected-(Y1-0-Pad3)") (class "Default")
      (node (ref "Y1") (pin "3") (pinfunction "0_3") (pintype "passive"))
    )
    (net (code "63") (name "unconnected-(Y1-0-Pad4)") (class "Default")
      (node (ref "Y1") (pin "4") (pinfunction "0_4") (pintype "passive"))
    )
  )
)
